# SigCapture2.net
KiCad netlist of a schematic drawn in Altium Designer
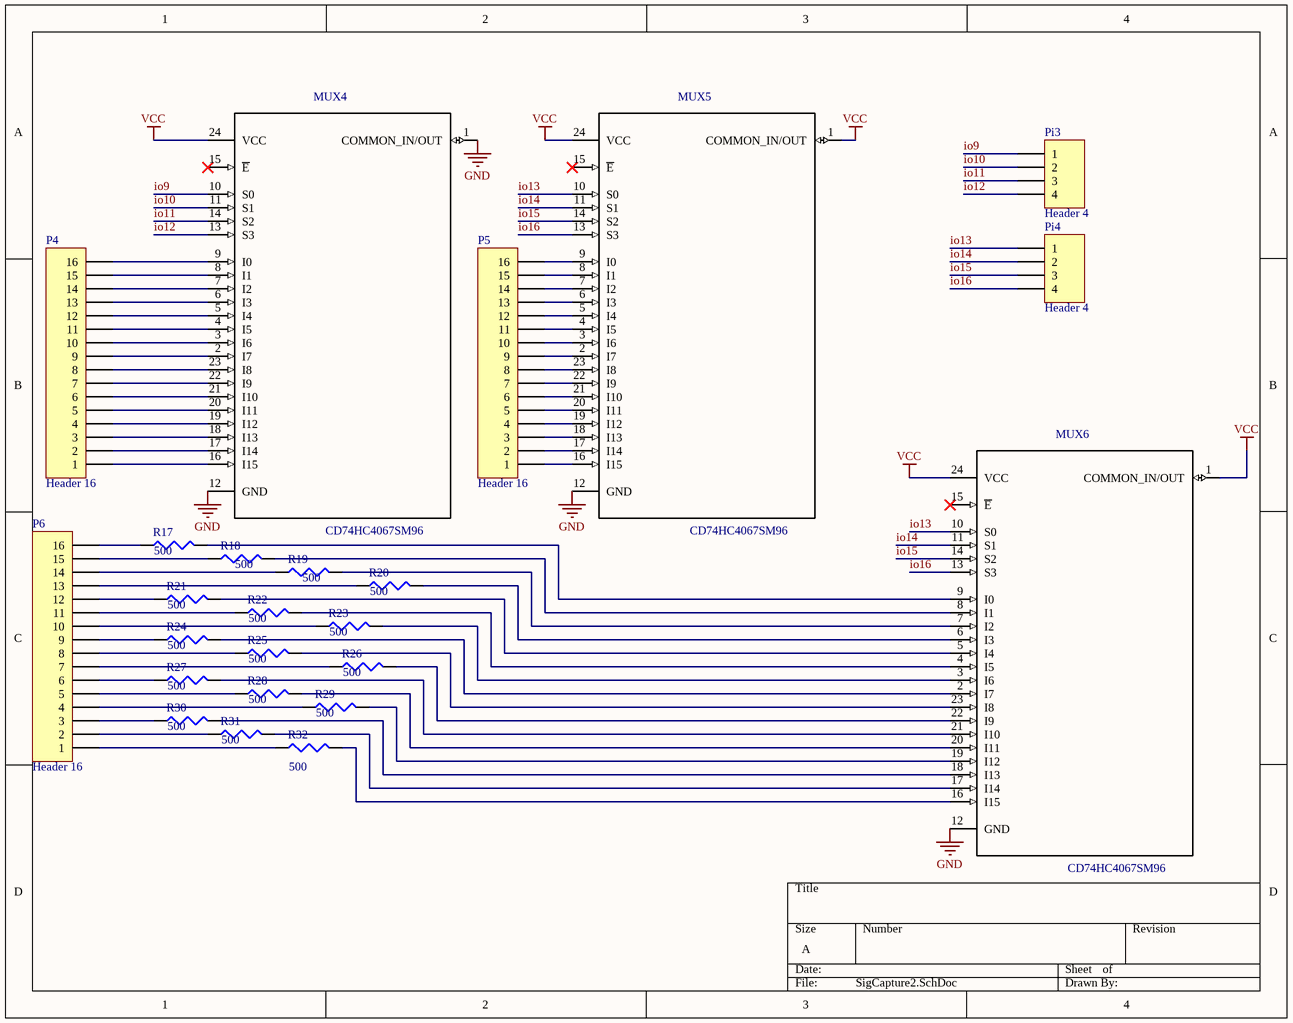
[diagram p0: SigCapture2.SchDoc]

(export (version "E")
  (design (tool "Eeschema 10.0.6"))
  (components
    (comp (ref "MUX4")
      (value "CD74HC4067SM96")
      (footprint "SOP65P780X200-24N")
      (description "High Speed CMOS 16-Channel Analog Multiplexer/Demultiplexer 24-SSOP -55 to 125")
      (fields (field (name "MF") "Texas Instruments"))
      (libsource (lib "CD74HC4067SM96") (part "CD74HC4067SM96"))
    )
    (comp (ref "MUX5")
      (value "CD74HC4067SM96")
      (footprint "SOP65P780X200-24N")
      (description "High Speed CMOS 16-Channel Analog Multiplexer/Demultiplexer 24-SSOP -55 to 125")
      (fields (field (name "MF") "Texas Instruments"))
      (libsource (lib "CD74HC4067SM96") (part "CD74HC4067SM96"))
    )
    (comp (ref "MUX6")
      (value "CD74HC4067SM96")
      (footprint "SOP65P780X200-24N")
      (description "High Speed CMOS 16-Channel Analog Multiplexer/Demultiplexer 24-SSOP -55 to 125")
      (fields (field (name "MF") "Texas Instruments"))
      (libsource (lib "CD74HC4067SM96") (part "CD74HC4067SM96"))
    )
    (comp (ref "P4")
      (value "Header 16")
      (footprint "HDR1X16")
      (description "Header, 16-Pin")
      (fields (field (name "PUBLISHER") "Altium Limited"))
      (libsource (lib "Miscellaneous Connectors") (part "Header 16"))
    )
    (comp (ref "P5")
      (value "Header 16")
      (footprint "HDR1X16")
      (description "Header, 16-Pin")
      (fields (field (name "PUBLISHER") "Altium Limited"))
      (libsource (lib "Miscellaneous Connectors") (part "Header 16"))
    )
    (comp (ref "P6")
      (value "Header 16")
      (footprint "HDR1X16")
      (description "Header, 16-Pin")
      (fields (field (name "PUBLISHER") "Altium Limited"))
      (libsource (lib "Miscellaneous Connectors") (part "Header 16"))
    )
    (comp (ref "Pi3")
      (value "Header 4")
      (footprint "HDR1X4")
      (description "Header, 4-Pin")
      (fields (field (name "PUBLISHER") "Altium Limited"))
      (libsource (lib "Miscellaneous Connectors") (part "Header 4"))
    )
    (comp (ref "Pi4")
      (value "Header 4")
      (footprint "HDR1X4")
      (description "Header, 4-Pin")
      (fields (field (name "PUBLISHER") "Altium Limited"))
      (libsource (lib "Miscellaneous Connectors") (part "Header 4"))
    )
    (comp (ref "R17")
      (value "500")
      (footprint "J1-0603")
      (description "Resistor")
      (fields (field (name "Comment") "Res3") (field (name "PUBLISHER") "Altium Limited"))
      (libsource (lib "Miscellaneous Devices") (part "Res3"))
    )
    (comp (ref "R18")
      (value "500")
      (footprint "J1-0603")
      (description "Resistor")
      (fields (field (name "Comment") "Res3") (field (name "PUBLISHER") "Altium Limited"))
      (libsource (lib "Miscellaneous Devices") (part "Res3"))
    )
    (comp (ref "R19")
      (value "500")
      (footprint "J1-0603")
      (description "Resistor")
      (fields (field (name "Comment") "Res3") (field (name "PUBLISHER") "Altium Limited"))
      (libsource (lib "Miscellaneous Devices") (part "Res3"))
    )
    (comp (ref "R20")
      (value "500")
      (footprint "J1-0603")
      (description "Resistor")
      (fields (field (name "Comment") "Res3") (field (name "PUBLISHER") "Altium Limited"))
      (libsource (lib "Miscellaneous Devices") (part "Res3"))
    )
    (comp (ref "R21")
      (value "500")
      (footprint "J1-0603")
      (description "Resistor")
      (fields (field (name "Comment") "Res3") (field (name "PUBLISHER") "Altium Limited"))
      (libsource (lib "Miscellaneous Devices") (part "Res3"))
    )
    (comp (ref "R22")
      (value "500")
      (footprint "J1-0603")
      (description "Resistor")
      (fields (field (name "Comment") "Res3") (field (name "PUBLISHER") "Altium Limited"))
      (libsource (lib "Miscellaneous Devices") (part "Res3"))
    )
    (comp (ref "R23")
      (value "500")
      (footprint "J1-0603")
      (description "Resistor")
      (fields (field (name "Comment") "Res3") (field (name "PUBLISHER") "Altium Limited"))
      (libsource (lib "Miscellaneous Devices") (part "Res3"))
    )
    (comp (ref "R24")
      (value "500")
      (footprint "J1-0603")
      (description "Resistor")
      (fields (field (name "Comment") "Res3") (field (name "PUBLISHER") "Altium Limited"))
      (libsource (lib "Miscellaneous Devices") (part "Res3"))
    )
    (comp (ref "R25")
      (value "500")
      (footprint "J1-0603")
      (description "Resistor")
      (fields (field (name "Comment") "Res3") (field (name "PUBLISHER") "Altium Limited"))
      (libsource (lib "Miscellaneous Devices") (part "Res3"))
    )
    (comp (ref "R26")
      (value "500")
      (footprint "J1-0603")
      (description "Resistor")
      (fields (field (name "Comment") "Res3") (field (name "PUBLISHER") "Altium Limited"))
      (libsource (lib "Miscellaneous Devices") (part "Res3"))
    )
    (comp (ref "R27")
      (value "500")
      (footprint "J1-0603")
      (description "Resistor")
      (fields (field (name "Comment") "Res3") (field (name "PUBLISHER") "Altium Limited"))
      (libsource (lib "Miscellaneous Devices") (part "Res3"))
    )
    (comp (ref "R28")
      (value "500")
      (footprint "J1-0603")
      (description "Resistor")
      (fields (field (name "Comment") "Res3") (field (name "PUBLISHER") "Altium Limited"))
      (libsource (lib "Miscellaneous Devices") (part "Res3"))
    )
    (comp (ref "R29")
      (value "500")
      (footprint "J1-0603")
      (description "Resistor")
      (fields (field (name "Comment") "Res3") (field (name "PUBLISHER") "Altium Limited"))
      (libsource (lib "Miscellaneous Devices") (part "Res3"))
    )
    (comp (ref "R30")
      (value "500")
      (footprint "J1-0603")
      (description "Resistor")
      (fields (field (name "Comment") "Res3") (field (name "PUBLISHER") "Altium Limited"))
      (libsource (lib "Miscellaneous Devices") (part "Res3"))
    )
    (comp (ref "R31")
      (value "500")
      (footprint "J1-0603")
      (description "Resistor")
      (fields (field (name "Comment") "Res3") (field (name "PUBLISHER") "Altium Limited"))
      (libsource (lib "Miscellaneous Devices") (part "Res3"))
    )
    (comp (ref "R32")
      (value "500")
      (footprint "J1-0603")
      (description "Resistor")
      (fields (field (name "Comment") "Res3") (field (name "PUBLISHER") "Altium Limited"))
      (libsource (lib "Miscellaneous Devices") (part "Res3"))
    )
  )
  (nets
    (net (code "1") (name "/io9") (class "Default")
      (node (ref "MUX4") (pin "10") (pinfunction "S0_10") (pintype "input"))
      (node (ref "Pi3") (pin "1") (pinfunction "1_1") (pintype "passive"))
    )
    (net (code "2") (name "/io10") (class "Default")
      (node (ref "MUX4") (pin "11") (pinfunction "S1_11") (pintype "input"))
      (node (ref "Pi3") (pin "2") (pinfunction "2_2") (pintype "passive"))
    )
    (net (code "3") (name "/io11") (class "Default")
      (node (ref "MUX4") (pin "14") (pinfunction "S2_14") (pintype "input"))
      (node (ref "Pi3") (pin "3") (pinfunction "3_3") (pintype "passive"))
    )
    (net (code "4") (name "/io12") (class "Default")
      (node (ref "MUX4") (pin "13") (pinfunction "S3_13") (pintype "input"))
      (node (ref "Pi3") (pin "4") (pinfunction "4_4") (pintype "passive"))
    )
    (net (code "5") (name "/io13") (class "Default")
      (node (ref "MUX5") (pin "10") (pinfunction "S0_10") (pintype "input"))
      (node (ref "MUX6") (pin "10") (pinfunction "S0_10") (pintype "input"))
      (node (ref "Pi4") (pin "1") (pinfunction "1_1") (pintype "passive"))
    )
    (net (code "6") (name "/io14") (class "Default")
      (node (ref "MUX5") (pin "11") (pinfunction "S1_11") (pintype "input"))
      (node (ref "MUX6") (pin "11") (pinfunction "S1_11") (pintype "input"))
      (node (ref "Pi4") (pin "2") (pinfunction "2_2") (pintype "passive"))
    )
    (net (code "7") (name "/io15") (class "Default")
      (node (ref "MUX5") (pin "14") (pinfunction "S2_14") (pintype "input"))
      (node (ref "MUX6") (pin "14") (pinfunction "S2_14") (pintype "input"))
      (node (ref "Pi4") (pin "3") (pinfunction "3_3") (pintype "passive"))
    )
    (net (code "8") (name "/io16") (class "Default")
      (node (ref "MUX5") (pin "13") (pinfunction "S3_13") (pintype "input"))
      (node (ref "MUX6") (pin "13") (pinfunction "S3_13") (pintype "input"))
      (node (ref "Pi4") (pin "4") (pinfunction "4_4") (pintype "passive"))
    )
    (net (code "9") (name "GND") (class "Default")
      (node (ref "MUX4") (pin "1") (pinfunction "COMMON_IN/OUT_1") (pintype "bidirectional"))
      (node (ref "MUX4") (pin "12") (pinfunction "GND_12") (pintype "passive"))
      (node (ref "MUX5") (pin "12") (pinfunction "GND_12") (pintype "passive"))
      (node (ref "MUX6") (pin "12") (pinfunction "GND_12") (pintype "passive"))
    )
    (net (code "10") (name "Net-(MUX4-I0)") (class "Default")
      (node (ref "MUX4") (pin "9") (pinfunction "I0_9") (pintype "input"))
      (node (ref "P4") (pin "16") (pinfunction "16_16") (pintype "passive"))
    )
    (net (code "11") (name "Net-(MUX4-I1)") (class "Default")
      (node (ref "MUX4") (pin "8") (pinfunction "I1_8") (pintype "input"))
      (node (ref "P4") (pin "15") (pinfunction "15_15") (pintype "passive"))
    )
    (net (code "12") (name "Net-(MUX4-I2)") (class "Default")
      (node (ref "MUX4") (pin "7") (pinfunction "I2_7") (pintype "input"))
      (node (ref "P4") (pin "14") (pinfunction "14_14") (pintype "passive"))
    )
    (net (code "13") (name "Net-(MUX4-I3)") (class "Default")
      (node (ref "MUX4") (pin "6") (pinfunction "I3_6") (pintype "input"))
      (node (ref "P4") (pin "13") (pinfunction "13_13") (pintype "passive"))
    )
    (net (code "14") (name "Net-(MUX4-I4)") (class "Default")
      (node (ref "MUX4") (pin "5") (pinfunction "I4_5") (pintype "input"))
      (node (ref "P4") (pin "12") (pinfunction "12_12") (pintype "passive"))
    )
    (net (code "15") (name "Net-(MUX4-I5)") (class "Default")
      (node (ref "MUX4") (pin "4") (pinfunction "I5_4") (pintype "input"))
      (node (ref "P4") (pin "11") (pinfunction "11_11") (pintype "passive"))
    )
    (net (code "16") (name "Net-(MUX4-I6)") (class "Default")
      (node (ref "MUX4") (pin "3") (pinfunction "I6_3") (pintype "input"))
      (node (ref "P4") (pin "10") (pinfunction "10_10") (pintype "passive"))
    )
    (net (code "17") (name "Net-(MUX4-I7)") (class "Default")
      (node (ref "MUX4") (pin "2") (pinfunction "I7_2") (pintype "input"))
      (node (ref "P4") (pin "9") (pinfunction "9_9") (pintype "passive"))
    )
    (net (code "18") (name "Net-(MUX4-I8)") (class "Default")
      (node (ref "MUX4") (pin "23") (pinfunction "I8_23") (pintype "input"))
      (node (ref "P4") (pin "8") (pinfunction "8_8") (pintype "passive"))
    )
    (net (code "19") (name "Net-(MUX4-I9)") (class "Default")
      (node (ref "MUX4") (pin "22") (pinfunction "I9_22") (pintype "input"))
      (node (ref "P4") (pin "7") (pinfunction "7_7") (pintype "passive"))
    )
    (net (code "20") (name "Net-(MUX4-I10)") (class "Default")
      (node (ref "MUX4") (pin "21") (pinfunction "I10_21") (pintype "input"))
      (node (ref "P4") (pin "6") (pinfunction "6_6") (pintype "passive"))
    )
    (net (code "21") (name "Net-(MUX4-I11)") (class "Default")
      (node (ref "MUX4") (pin "20") (pinfunction "I11_20") (pintype "input"))
      (node (ref "P4") (pin "5") (pinfunction "5_5") (pintype "passive"))
    )
    (net (code "22") (name "Net-(MUX4-I12)") (class "Default")
      (node (ref "MUX4") (pin "19") (pinfunction "I12_19") (pintype "input"))
      (node (ref "P4") (pin "4") (pinfunction "4_4") (pintype "passive"))
    )
    (net (code "23") (name "Net-(MUX4-I13)") (class "Default")
      (node (ref "MUX4") (pin "18") (pinfunction "I13_18") (pintype "input"))
      (node (ref "P4") (pin "3") (pinfunction "3_3") (pintype "passive"))
    )
    (net (code "24") (name "Net-(MUX4-I14)") (class "Default")
      (node (ref "MUX4") (pin "17") (pinfunction "I14_17") (pintype "input"))
      (node (ref "P4") (pin "2") (pinfunction "2_2") (pintype "passive"))
    )
    (net (code "25") (name "Net-(MUX4-I15)") (class "Default")
      (node (ref "MUX4") (pin "16") (pinfunction "I15_16") (pintype "input"))
      (node (ref "P4") (pin "1") (pinfunction "1_1") (pintype "passive"))
    )
    (net (code "26") (name "Net-(MUX5-I0)") (class "Default")
      (node (ref "MUX5") (pin "9") (pinfunction "I0_9") (pintype "input"))
      (node (ref "P5") (pin "16") (pinfunction "16_16") (pintype "passive"))
    )
    (net (code "27") (name "Net-(MUX5-I1)") (class "Default")
      (node (ref "MUX5") (pin "8") (pinfunction "I1_8") (pintype "input"))
      (node (ref "P5") (pin "15") (pinfunction "15_15") (pintype "passive"))
    )
    (net (code "28") (name "Net-(MUX5-I2)") (class "Default")
      (node (ref "MUX5") (pin "7") (pinfunction "I2_7") (pintype "input"))
      (node (ref "P5") (pin "14") (pinfunction "14_14") (pintype "passive"))
    )
    (net (code "29") (name "Net-(MUX5-I3)") (class "Default")
      (node (ref "MUX5") (pin "6") (pinfunction "I3_6") (pintype "input"))
      (node (ref "P5") (pin "13") (pinfunction "13_13") (pintype "passive"))
    )
    (net (code "30") (name "Net-(MUX5-I4)") (class "Default")
      (node (ref "MUX5") (pin "5") (pinfunction "I4_5") (pintype "input"))
      (node (ref "P5") (pin "12") (pinfunction "12_12") (pintype "passive"))
    )
    (net (code "31") (name "Net-(MUX5-I5)") (class "Default")
      (node (ref "MUX5") (pin "4") (pinfunction "I5_4") (pintype "input"))
      (node (ref "P5") (pin "11") (pinfunction "11_11") (pintype "passive"))
    )
    (net (code "32") (name "Net-(MUX5-I6)") (class "Default")
      (node (ref "MUX5") (pin "3") (pinfunction "I6_3") (pintype "input"))
      (node (ref "P5") (pin "10") (pinfunction "10_10") (pintype "passive"))
    )
    (net (code "33") (name "Net-(MUX5-I7)") (class "Default")
      (node (ref "MUX5") (pin "2") (pinfunction "I7_2") (pintype "input"))
      (node (ref "P5") (pin "9") (pinfunction "9_9") (pintype "passive"))
    )
    (net (code "34") (name "Net-(MUX5-I8)") (class "Default")
      (node (ref "MUX5") (pin "23") (pinfunction "I8_23") (pintype "input"))
      (node (ref "P5") (pin "8") (pinfunction "8_8") (pintype "passive"))
    )
    (net (code "35") (name "Net-(MUX5-I9)") (class "Default")
      (node (ref "MUX5") (pin "22") (pinfunction "I9_22") (pintype "input"))
      (node (ref "P5") (pin "7") (pinfunction "7_7") (pintype "passive"))
    )
    (net (code "36") (name "Net-(MUX5-I10)") (class "Default")
      (node (ref "MUX5") (pin "21") (pinfunction "I10_21") (pintype "input"))
      (node (ref "P5") (pin "6") (pinfunction "6_6") (pintype "passive"))
    )
    (net (code "37") (name "Net-(MUX5-I11)") (class "Default")
      (node (ref "MUX5") (pin "20") (pinfunction "I11_20") (pintype "input"))
      (node (ref "P5") (pin "5") (pinfunction "5_5") (pintype "passive"))
    )
    (net (code "38") (name "Net-(MUX5-I12)") (class "Default")
      (node (ref "MUX5") (pin "19") (pinfunction "I12_19") (pintype "input"))
      (node (ref "P5") (pin "4") (pinfunction "4_4") (pintype "passive"))
    )
    (net (code "39") (name "Net-(MUX5-I13)") (class "Default")
      (node (ref "MUX5") (pin "18") (pinfunction "I13_18") (pintype "input"))
      (node (ref "P5") (pin "3") (pinfunction "3_3") (pintype "passive"))
    )
    (net (code "40") (name "Net-(MUX5-I14)") (class "Default")
      (node (ref "MUX5") (pin "17") (pinfunction "I14_17") (pintype "input"))
      (node (ref "P5") (pin "2") (pinfunction "2_2") (pintype "passive"))
    )
    (net (code "41") (name "Net-(MUX5-I15)") (class "Default")
      (node (ref "MUX5") (pin "16") (pinfunction "I15_16") (pintype "input"))
      (node (ref "P5") (pin "1") (pinfunction "1_1") (pintype "passive"))
    )
    (net (code "42") (name "Net-(MUX6-I0)") (class "Default")
      (node (ref "MUX6") (pin "9") (pinfunction "I0_9") (pintype "input"))
      (node (ref "R17") (pin "2") (pinfunction "2_2") (pintype "passive"))
    )
    (net (code "43") (name "Net-(MUX6-I1)") (class "Default")
      (node (ref "MUX6") (pin "8") (pinfunction "I1_8") (pintype "input"))
      (node (ref "R18") (pin "2") (pinfunction "2_2") (pintype "passive"))
    )
    (net (code "44") (name "Net-(MUX6-I2)") (class "Default")
      (node (ref "MUX6") (pin "7") (pinfunction "I2_7") (pintype "input"))
      (node (ref "R19") (pin "2") (pinfunction "2_2") (pintype "passive"))
    )
    (net (code "45") (name "Net-(MUX6-I3)") (class "Default")
      (node (ref "MUX6") (pin "6") (pinfunction "I3_6") (pintype "input"))
      (node (ref "R20") (pin "2") (pinfunction "2_2") (pintype "passive"))
    )
    (net (code "46") (name "Net-(MUX6-I4)") (class "Default")
      (node (ref "MUX6") (pin "5") (pinfunction "I4_5") (pintype "input"))
      (node (ref "R21") (pin "2") (pinfunction "2_2") (pintype "passive"))
    )
    (net (code "47") (name "Net-(MUX6-I5)") (class "Default")
      (node (ref "MUX6") (pin "4") (pinfunction "I5_4") (pintype "input"))
      (node (ref "R22") (pin "2") (pinfunction "2_2") (pintype "passive"))
    )
    (net (code "48") (name "Net-(MUX6-I6)") (class "Default")
      (node (ref "MUX6") (pin "3") (pinfunction "I6_3") (pintype "input"))
      (node (ref "R23") (pin "2") (pinfunction "2_2") (pintype "passive"))
    )
    (net (code "49") (name "Net-(MUX6-I7)") (class "Default")
      (node (ref "MUX6") (pin "2") (pinfunction "I7_2") (pintype "input"))
      (node (ref "R24") (pin "2") (pinfunction "2_2") (pintype "passive"))
    )
    (net (code "50") (name "Net-(MUX6-I8)") (class "Default")
      (node (ref "MUX6") (pin "23") (pinfunction "I8_23") (pintype "input"))
      (node (ref "R25") (pin "2") (pinfunction "2_2") (pintype "passive"))
    )
    (net (code "51") (name "Net-(MUX6-I9)") (class "Default")
      (node (ref "MUX6") (pin "22") (pinfunction "I9_22") (pintype "input"))
      (node (ref "R26") (pin "2") (pinfunction "2_2") (pintype "passive"))
    )
    (net (code "52") (name "Net-(MUX6-I10)") (class "Default")
      (node (ref "MUX6") (pin "21") (pinfunction "I10_21") (pintype "input"))
      (node (ref "R27") (pin "2") (pinfunction "2_2") (pintype "passive"))
    )
    (net (code "53") (name "Net-(MUX6-I11)") (class "Default")
      (node (ref "MUX6") (pin "20") (pinfunction "I11_20") (pintype "input"))
      (node (ref "R28") (pin "2") (pinfunction "2_2") (pintype "passive"))
    )
    (net (code "54") (name "Net-(MUX6-I12)") (class "Default")
      (node (ref "MUX6") (pin "19") (pinfunction "I12_19") (pintype "input"))
      (node (ref "R29") (pin "2") (pinfunction "2_2") (pintype "passive"))
    )
    (net (code "55") (name "Net-(MUX6-I13)") (class "Default")
      (node (ref "MUX6") (pin "18") (pinfunction "I13_18") (pintype "input"))
      (node (ref "R30") (pin "2") (pinfunction "2_2") (pintype "passive"))
    )
    (net (code "56") (name "Net-(MUX6-I14)") (class "Default")
      (node (ref "MUX6") (pin "17") (pinfunction "I14_17") (pintype "input"))
      (node (ref "R31") (pin "2") (pinfunction "2_2") (pintype "passive"))
    )
    (net (code "57") (name "Net-(MUX6-I15)") (class "Default")
      (node (ref "MUX6") (pin "16") (pinfunction "I15_16") (pintype "input"))
      (node (ref "R32") (pin "2") (pinfunction "2_2") (pintype "passive"))
    )
    (net (code "58") (name "Net-(P6-Pad1)") (class "Default")
      (node (ref "P6") (pin "1") (pinfunction "1_1") (pintype "passive"))
      (node (ref "R32") (pin "1") (pinfunction "1_1") (pintype "passive"))
    )
    (net (code "59") (name "Net-(P6-Pad2)") (class "Default")
      (node (ref "P6") (pin "2") (pinfunction "2_2") (pintype "passive"))
      (node (ref "R31") (pin "1") (pinfunction "1_1") (pintype "passive"))
    )
    (net (code "60") (name "Net-(P6-Pad3)") (class "Default")
      (node (ref "P6") (pin "3") (pinfunction "3_3") (pintype "passive"))
      (node (ref "R30") (pin "1") (pinfunction "1_1") (pintype "passive"))
    )
    (net (code "61") (name "Net-(P6-Pad4)") (class "Default")
      (node (ref "P6") (pin "4") (pinfunction "4_4") (pintype "passive"))
      (node (ref "R29") (pin "1") (pinfunction "1_1") (pintype "passive"))
    )
    (net (code "62") (name "Net-(P6-Pad5)") (class "Default")
      (node (ref "P6") (pin "5") (pinfunction "5_5") (pintype "passive"))
      (node (ref "R28") (pin "1") (pinfunction "1_1") (pintype "passive"))
    )
    (net (code "63") (name "Net-(P6-Pad6)") (class "Default")
      (node (ref "P6") (pin "6") (pinfunction "6_6") (pintype "passive"))
      (node (ref "R27") (pin "1") (pinfunction "1_1") (pintype "passive"))
    )
    (net (code "64") (name "Net-(P6-Pad7)") (class "Default")
      (node (ref "P6") (pin "7") (pinfunction "7_7") (pintype "passive"))
      (node (ref "R26") (pin "1") (pinfunction "1_1") (pintype "passive"))
    )
    (net (code "65") (name "Net-(P6-Pad8)") (class "Default")
      (node (ref "P6") (pin "8") (pinfunction "8_8") (pintype "passive"))
      (node (ref "R25") (pin "1") (pinfunction "1_1") (pintype "passive"))
    )
    (net (code "66") (name "Net-(P6-Pad9)") (class "Default")
      (node (ref "P6") (pin "9") (pinfunction "9_9") (pintype "passive"))
      (node (ref "R24") (pin "1") (pinfunction "1_1") (pintype "passive"))
    )
    (net (code "67") (name "Net-(P6-Pad10)") (class "Default")
      (node (ref "P6") (pin "10") (pinfunction "10_10") (pintype "passive"))
      (node (ref "R23") (pin "1") (pinfunction "1_1") (pintype "passive"))
    )
    (net (code "68") (name "Net-(P6-Pad11)") (class "Default")
      (node (ref "P6") (pin "11") (pinfunction "11_11") (pintype "passive"))
      (node (ref "R22") (pin "1") (pinfunction "1_1") (pintype "passive"))
    )
    (net (code "69") (name "Net-(P6-Pad12)") (class "Default")
      (node (ref "P6") (pin "12") (pinfunction "12_12") (pintype "passive"))
      (node (ref "R21") (pin "1") (pinfunction "1_1") (pintype "passive"))
    )
    (net (code "70") (name "Net-(P6-Pad13)") (class "Default")
      (node (ref "P6") (pin "13") (pinfunction "13_13") (pintype "passive"))
      (node (ref "R20") (pin "1") (pinfunction "1_1") (pintype "passive"))
    )
    (net (code "71") (name "Net-(P6-Pad14)") (class "Default")
      (node (ref "P6") (pin "14") (pinfunction "14_14") (pintype "passive"))
      (node (ref "R19") (pin "1") (pinfunction "1_1") (pintype "passive"))
    )
    (net (code "72") (name "Net-(P6-Pad15)") (class "Default")
      (node (ref "P6") (pin "15") (pinfunction "15_15") (pintype "passive"))
      (node (ref "R18") (pin "1") (pinfunction "1_1") (pintype "passive"))
    )
    (net (code "73") (name "Net-(P6-Pad16)") (class "Default")
      (node (ref "P6") (pin "16") (pinfunction "16_16") (pintype "passive"))
      (node (ref "R17") (pin "1") (pinfunction "1_1") (pintype "passive"))
    )
    (net (code "74") (name "VCC") (class "Default")
      (node (ref "MUX4") (pin "24") (pinfunction "VCC_24") (pintype "power_in"))
      (node (ref "MUX5") (pin "1") (pinfunction "COMMON_IN/OUT_1") (pintype "bidirectional"))
      (node (ref "MUX5") (pin "24") (pinfunction "VCC_24") (pintype "power_in"))
      (node (ref "MUX6") (pin "1") (pinfunction "COMMON_IN/OUT_1") (pintype "bidirectional"))
      (node (ref "MUX6") (pin "24") (pinfunction "VCC_24") (pintype "power_in"))
    )
    (net (code "75") (name "unconnected-(MUX4-~{E}-Pad15)") (class "Default")
      (node (ref "MUX4") (pin "15") (pinfunction "~{E}_15") (pintype "input+no_connect"))
    )
    (net (code "76") (name "unconnected-(MUX5-~{E}-Pad15)") (class "Default")
      (node (ref "MUX5") (pin "15") (pinfunction "~{E}_15") (pintype "input+no_connect"))
    )
    (net (code "77") (name "unconnected-(MUX6-~{E}-Pad15)") (class "Default")
      (node (ref "MUX6") (pin "15") (pinfunction "~{E}_15") (pintype "input+no_connect"))
    )
  )
)
